# main.net
KiCad netlist of a schematic drawn in Altium Designer
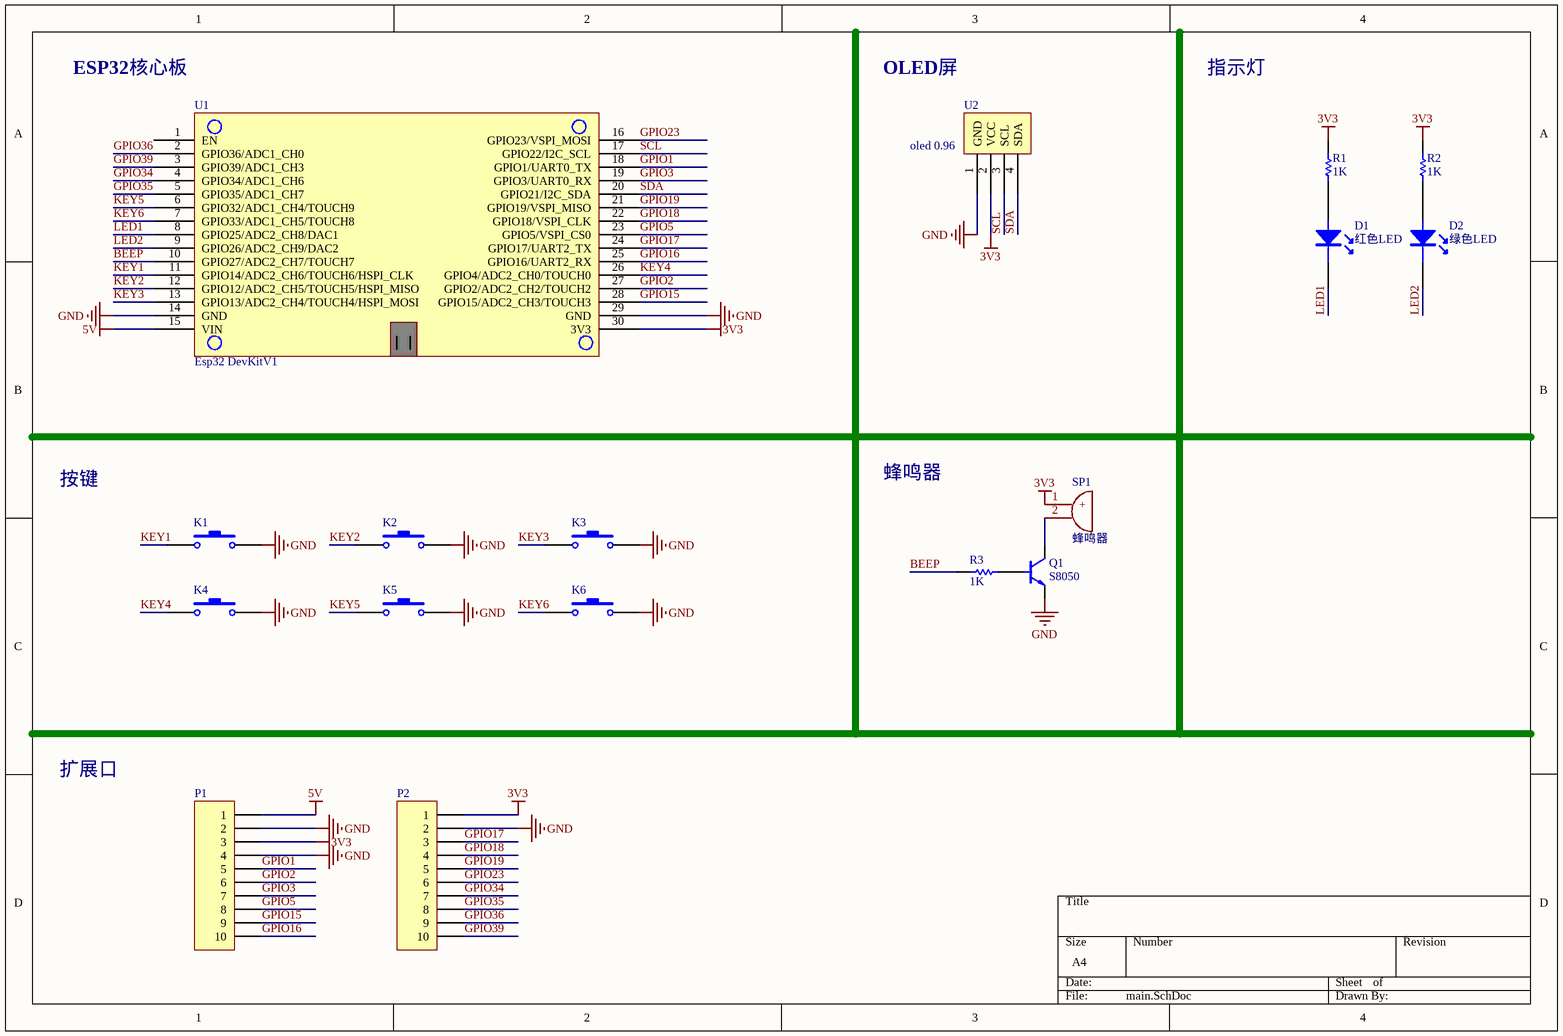
[diagram p0: main.SchDoc]

(export (version "E")
  (design (tool "Eeschema 10.0.6"))
  (components
    (comp (ref "D1") (value "红色LED") (footprint "LED_3mm") (libsource (lib "pcb_library_jdh") (part "LED")))
    (comp (ref "D2") (value "绿色LED") (footprint "LED_3mm") (libsource (lib "pcb_library_jdh") (part "LED")))
    (comp (ref "K1")
      (value "KEY_12x12x7.3")
      (footprint "KEY-12x12")
      (libsource (lib "pcb_library_jdh") (part "KEY_12x12x7.3"))
    )
    (comp (ref "K2")
      (value "KEY_12x12x7.3")
      (footprint "KEY-12x12")
      (libsource (lib "pcb_library_jdh") (part "KEY_12x12x7.3"))
    )
    (comp (ref "K3")
      (value "KEY_12x12x7.3")
      (footprint "KEY-12x12")
      (libsource (lib "pcb_library_jdh") (part "KEY_12x12x7.3"))
    )
    (comp (ref "K4")
      (value "KEY_12x12x7.3")
      (footprint "KEY-12x12")
      (libsource (lib "pcb_library_jdh") (part "KEY_12x12x7.3"))
    )
    (comp (ref "K5")
      (value "KEY_12x12x7.3")
      (footprint "KEY-12x12")
      (libsource (lib "pcb_library_jdh") (part "KEY_12x12x7.3"))
    )
    (comp (ref "K6")
      (value "KEY_12x12x7.3")
      (footprint "KEY-12x12")
      (libsource (lib "pcb_library_jdh") (part "KEY_12x12x7.3"))
    )
    (comp (ref "P1")
      (value "Header10")
      (footprint "HDR1X10_2.54")
      (libsource (lib "pcb_library_jdh") (part "Header10"))
    )
    (comp (ref "P2")
      (value "Header10")
      (footprint "HDR1X10_2.54")
      (libsource (lib "pcb_library_jdh") (part "Header10"))
    )
    (comp (ref "Q1")
      (value "S8050")
      (footprint "TO-226-AA")
      (libsource (lib "pcb_library_jdh") (part "S8050"))
    )
    (comp (ref "R1") (value "1K") (footprint "AXIAL-0.3") (libsource (lib "pcb_library_jdh") (part "电阻")))
    (comp (ref "R2") (value "1K") (footprint "AXIAL-0.3") (libsource (lib "pcb_library_jdh") (part "电阻")))
    (comp (ref "R3") (value "1K") (footprint "AXIAL-0.3") (libsource (lib "pcb_library_jdh") (part "电阻")))
    (comp (ref "SP1")
      (value "蜂鸣器")
      (footprint "BUZZER-12095-3V")
      (libsource (lib "pcb_library_jdh") (part "BUZZER-12095-3V"))
    )
    (comp (ref "U1")
      (value "Esp32 DevKitV1")
      (footprint "Esp32DevKitV1")
      (libsource (lib "pcb_library_jdh") (part "Esp32DevKitV1"))
    )
    (comp (ref "U2")
      (value "oled 0.96")
      (footprint "oled0.96i2c")
      (libsource (lib "pcb_library_jdh") (part "oled0.96i2c"))
    )
  )
  (nets
    (net (code "1") (name "/BEEP") (class "Default")
      (node (ref "R3") (pin "2") (pinfunction "2_2") (pintype "passive"))
      (node (ref "U1") (pin "10") (pinfunction "GPIO27/ADC2_CH7/TOUCH7_10") (pintype "passive"))
    )
    (net (code "2") (name "/GPIO1") (class "Default")
      (node (ref "P1") (pin "5") (pinfunction "5_5") (pintype "passive"))
      (node (ref "U1") (pin "18") (pinfunction "GPIO1/UART0_TX_18") (pintype "passive"))
    )
    (net (code "3") (name "/GPIO2") (class "Default")
      (node (ref "P1") (pin "6") (pinfunction "6_6") (pintype "passive"))
      (node (ref "U1") (pin "27") (pinfunction "GPIO2/ADC2_CH2/TOUCH2_27") (pintype "passive"))
    )
    (net (code "4") (name "/GPIO3") (class "Default")
      (node (ref "P1") (pin "7") (pinfunction "7_7") (pintype "passive"))
      (node (ref "U1") (pin "19") (pinfunction "GPIO3/UART0_RX_19") (pintype "passive"))
    )
    (net (code "5") (name "/GPIO5") (class "Default")
      (node (ref "P1") (pin "8") (pinfunction "8_8") (pintype "passive"))
      (node (ref "U1") (pin "23") (pinfunction "GPIO5/VSPI_CS0_23") (pintype "passive"))
    )
    (net (code "6") (name "/GPIO15") (class "Default")
      (node (ref "P1") (pin "9") (pinfunction "9_9") (pintype "passive"))
      (node (ref "U1") (pin "28") (pinfunction "GPIO15/ADC2_CH3/TOUCH3_28") (pintype "passive"))
    )
    (net (code "7") (name "/GPIO16") (class "Default")
      (node (ref "P1") (pin "10") (pinfunction "10_10") (pintype "passive"))
      (node (ref "U1") (pin "25") (pinfunction "GPIO16/UART2_RX_25") (pintype "passive"))
    )
    (net (code "8") (name "/GPIO17") (class "Default")
      (node (ref "P2") (pin "3") (pinfunction "3_3") (pintype "passive"))
      (node (ref "U1") (pin "24") (pinfunction "GPIO17/UART2_TX_24") (pintype "passive"))
    )
    (net (code "9") (name "/GPIO18") (class "Default")
      (node (ref "P2") (pin "4") (pinfunction "4_4") (pintype "passive"))
      (node (ref "U1") (pin "22") (pinfunction "GPIO18/VSPI_CLK_22") (pintype "passive"))
    )
    (net (code "10") (name "/GPIO19") (class "Default")
      (node (ref "P2") (pin "5") (pinfunction "5_5") (pintype "passive"))
      (node (ref "U1") (pin "21") (pinfunction "GPIO19/VSPI_MISO_21") (pintype "passive"))
    )
    (net (code "11") (name "/GPIO23") (class "Default")
      (node (ref "P2") (pin "6") (pinfunction "6_6") (pintype "passive"))
      (node (ref "U1") (pin "16") (pinfunction "GPIO23/VSPI_MOSI_16") (pintype "passive"))
    )
    (net (code "12") (name "/GPIO34") (class "Default")
      (node (ref "P2") (pin "7") (pinfunction "7_7") (pintype "passive"))
      (node (ref "U1") (pin "4") (pinfunction "GPIO34/ADC1_CH6_4") (pintype "passive"))
    )
    (net (code "13") (name "/GPIO35") (class "Default")
      (node (ref "P2") (pin "8") (pinfunction "8_8") (pintype "passive"))
      (node (ref "U1") (pin "5") (pinfunction "GPIO35/ADC1_CH7_5") (pintype "passive"))
    )
    (net (code "14") (name "/GPIO36") (class "Default")
      (node (ref "P2") (pin "9") (pinfunction "9_9") (pintype "passive"))
      (node (ref "U1") (pin "2") (pinfunction "GPIO36/ADC1_CH0_2") (pintype "passive"))
    )
    (net (code "15") (name "/GPIO39") (class "Default")
      (node (ref "P2") (pin "10") (pinfunction "10_10") (pintype "passive"))
      (node (ref "U1") (pin "3") (pinfunction "GPIO39/ADC1_CH3_3") (pintype "passive"))
    )
    (net (code "16") (name "/KEY1") (class "Default")
      (node (ref "K1") (pin "1") (pinfunction "1_1") (pintype "passive"))
      (node (ref "U1") (pin "11") (pinfunction "GPIO14/ADC2_CH6/TOUCH6/HSPI_CLK_11") (pintype "passive"))
    )
    (net (code "17") (name "/KEY2") (class "Default")
      (node (ref "K2") (pin "1") (pinfunction "1_1") (pintype "passive"))
      (node (ref "U1") (pin "12") (pinfunction "GPIO12/ADC2_CH5/TOUCH5/HSPI_MISO_12") (pintype "passive"))
    )
    (net (code "18") (name "/KEY3") (class "Default")
      (node (ref "K3") (pin "1") (pinfunction "1_1") (pintype "passive"))
      (node (ref "U1") (pin "13") (pinfunction "GPIO13/ADC2_CH4/TOUCH4/HSPI_MOSI_13") (pintype "passive"))
    )
    (net (code "19") (name "/KEY4") (class "Default")
      (node (ref "K4") (pin "1") (pinfunction "1_1") (pintype "passive"))
      (node (ref "U1") (pin "26") (pinfunction "GPIO4/ADC2_CH0/TOUCH0_26") (pintype "passive"))
    )
    (net (code "20") (name "/KEY5") (class "Default")
      (node (ref "K5") (pin "1") (pinfunction "1_1") (pintype "passive"))
      (node (ref "U1") (pin "6") (pinfunction "GPIO32/ADC1_CH4/TOUCH9_6") (pintype "passive"))
    )
    (net (code "21") (name "/KEY6") (class "Default")
      (node (ref "K6") (pin "1") (pinfunction "1_1") (pintype "passive"))
      (node (ref "U1") (pin "7") (pinfunction "GPIO33/ADC1_CH5/TOUCH8_7") (pintype "passive"))
    )
    (net (code "22") (name "/LED1") (class "Default")
      (node (ref "D1") (pin "2") (pinfunction "2_2") (pintype "passive"))
      (node (ref "U1") (pin "8") (pinfunction "GPIO25/ADC2_CH8/DAC1_8") (pintype "passive"))
    )
    (net (code "23") (name "/LED2") (class "Default")
      (node (ref "D2") (pin "2") (pinfunction "2_2") (pintype "passive"))
      (node (ref "U1") (pin "9") (pinfunction "GPIO26/ADC2_CH9/DAC2_9") (pintype "passive"))
    )
    (net (code "24") (name "/SCL") (class "Default")
      (node (ref "U1") (pin "17") (pinfunction "GPIO22/I2C_SCL_17") (pintype "passive"))
      (node (ref "U2") (pin "3") (pinfunction "SCL_3") (pintype "passive"))
    )
    (net (code "25") (name "/SDA") (class "Default")
      (node (ref "U1") (pin "20") (pinfunction "GPIO21/I2C_SDA_20") (pintype "passive"))
      (node (ref "U2") (pin "4") (pinfunction "SDA_4") (pintype "passive"))
    )
    (net (code "26") (name "3V3") (class "Default")
      (node (ref "P1") (pin "3") (pinfunction "3_3") (pintype "passive"))
      (node (ref "P2") (pin "1") (pinfunction "1_1") (pintype "passive"))
      (node (ref "R1") (pin "2") (pinfunction "2_2") (pintype "passive"))
      (node (ref "R2") (pin "2") (pinfunction "2_2") (pintype "passive"))
      (node (ref "SP1") (pin "1") (pinfunction "+_1") (pintype "passive"))
      (node (ref "U1") (pin "30") (pinfunction "3V3_30") (pintype "passive"))
      (node (ref "U2") (pin "2") (pinfunction "VCC_2") (pintype "passive"))
    )
    (net (code "27") (name "5V") (class "Default")
      (node (ref "P1") (pin "1") (pinfunction "1_1") (pintype "passive"))
      (node (ref "U1") (pin "15") (pinfunction "VIN_15") (pintype "passive"))
    )
    (net (code "28") (name "GND") (class "Default")
      (node (ref "K1") (pin "2") (pinfunction "2_2") (pintype "passive"))
      (node (ref "K2") (pin "2") (pinfunction "2_2") (pintype "passive"))
      (node (ref "K3") (pin "2") (pinfunction "2_2") (pintype "passive"))
      (node (ref "K4") (pin "2") (pinfunction "2_2") (pintype "passive"))
      (node (ref "K5") (pin "2") (pinfunction "2_2") (pintype "passive"))
      (node (ref "K6") (pin "2") (pinfunction "2_2") (pintype "passive"))
      (node (ref "P1") (pin "2") (pinfunction "2_2") (pintype "passive"))
      (node (ref "P1") (pin "4") (pinfunction "4_4") (pintype "passive"))
      (node (ref "P2") (pin "2") (pinfunction "2_2") (pintype "passive"))
      (node (ref "Q1") (pin "1") (pinfunction "E_1") (pintype "passive"))
      (node (ref "U1") (pin "14") (pinfunction "GND_14") (pintype "passive"))
      (node (ref "U1") (pin "29") (pinfunction "GND_29") (pintype "passive"))
      (node (ref "U2") (pin "1") (pinfunction "GND_1") (pintype "passive"))
    )
    (net (code "29") (name "Net-(D1-Pad1)") (class "Default")
      (node (ref "D1") (pin "1") (pinfunction "1_1") (pintype "passive"))
      (node (ref "R1") (pin "1") (pinfunction "1_1") (pintype "passive"))
    )
    (net (code "30") (name "Net-(D2-Pad1)") (class "Default")
      (node (ref "D2") (pin "1") (pinfunction "1_1") (pintype "passive"))
      (node (ref "R2") (pin "1") (pinfunction "1_1") (pintype "passive"))
    )
    (net (code "31") (name "Net-(Q1-B)") (class "Default")
      (node (ref "Q1") (pin "2") (pinfunction "B_2") (pintype "passive"))
      (node (ref "R3") (pin "1") (pinfunction "1_1") (pintype "passive"))
    )
    (net (code "32") (name "Net-(Q1-C)") (class "Default")
      (node (ref "Q1") (pin "3") (pinfunction "C_3") (pintype "passive"))
      (node (ref "SP1") (pin "2") (pinfunction "-_2") (pintype "passive"))
    )
    (net (code "33") (name "unconnected-(U1-EN-Pad1)") (class "Default")
      (node (ref "U1") (pin "1") (pinfunction "EN_1") (pintype "passive"))
    )
  )
)
